# 3-ADC.net
KiCad netlist of a schematic drawn in Altium Designer
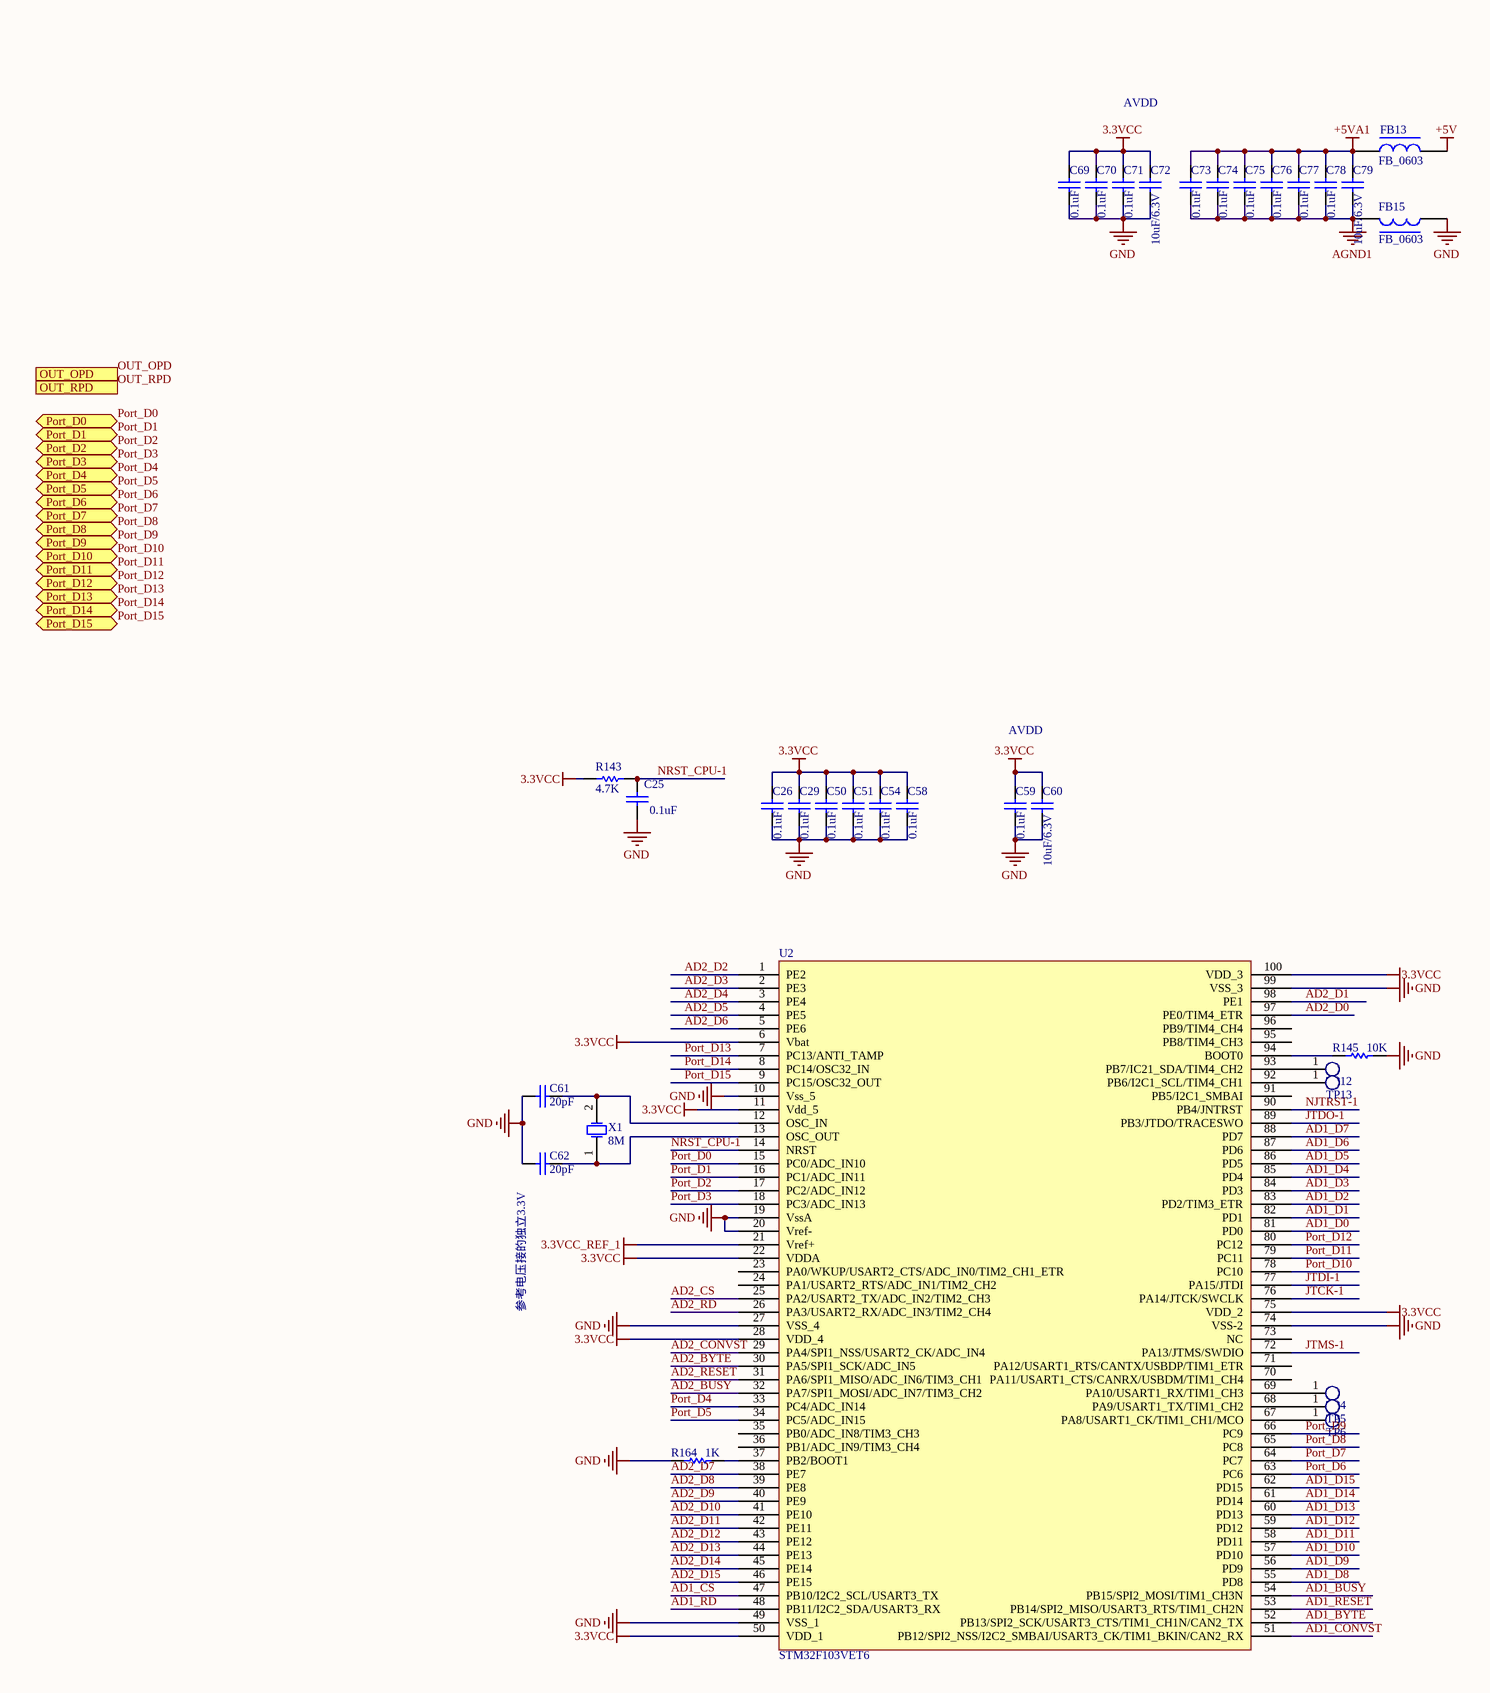
[diagram p0: 3-ADC.SchDoc, top left]
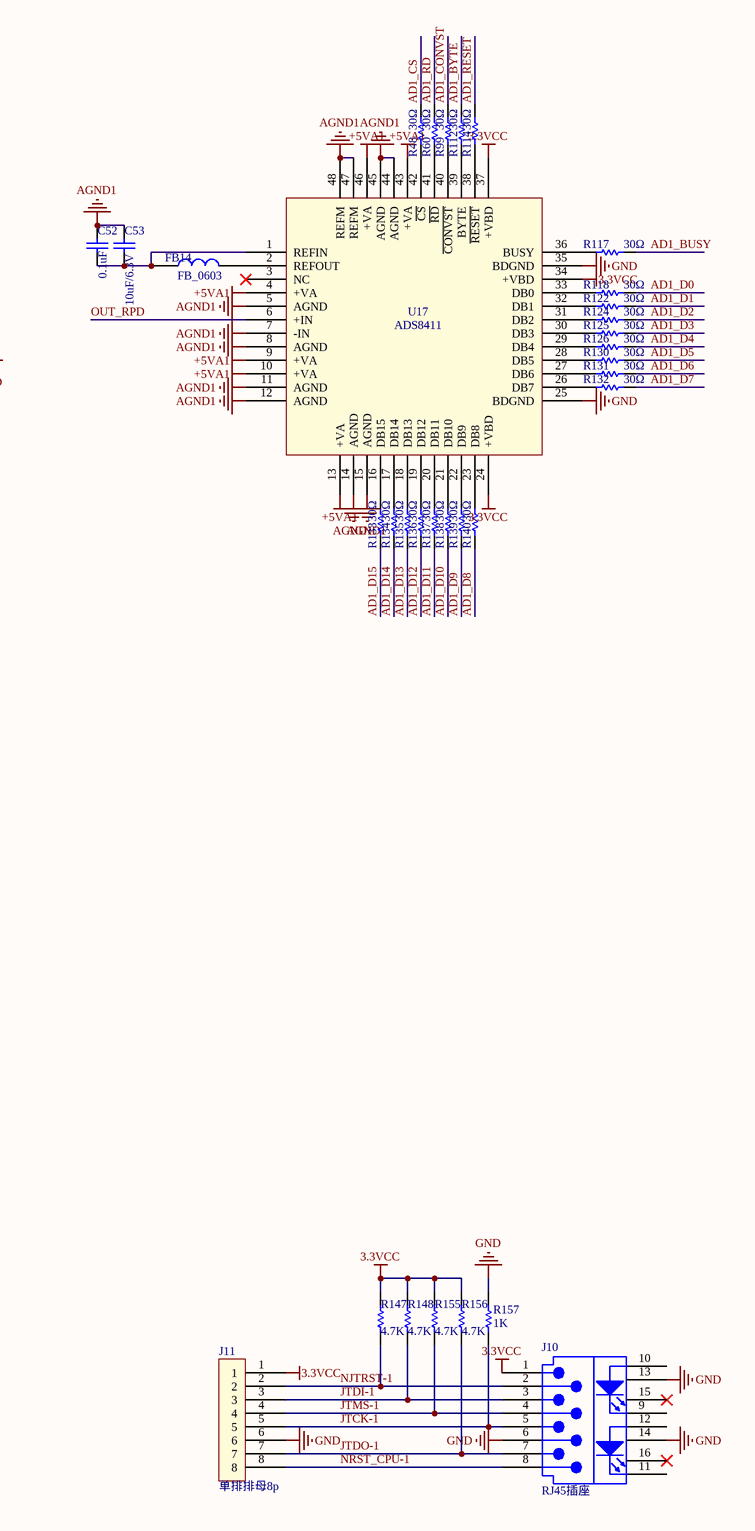
[diagram p1: 3-ADC.SchDoc, top right]
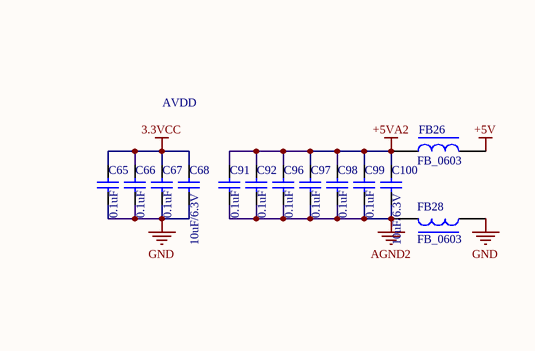
[diagram p2: 3-ADC.SchDoc, bottom left]
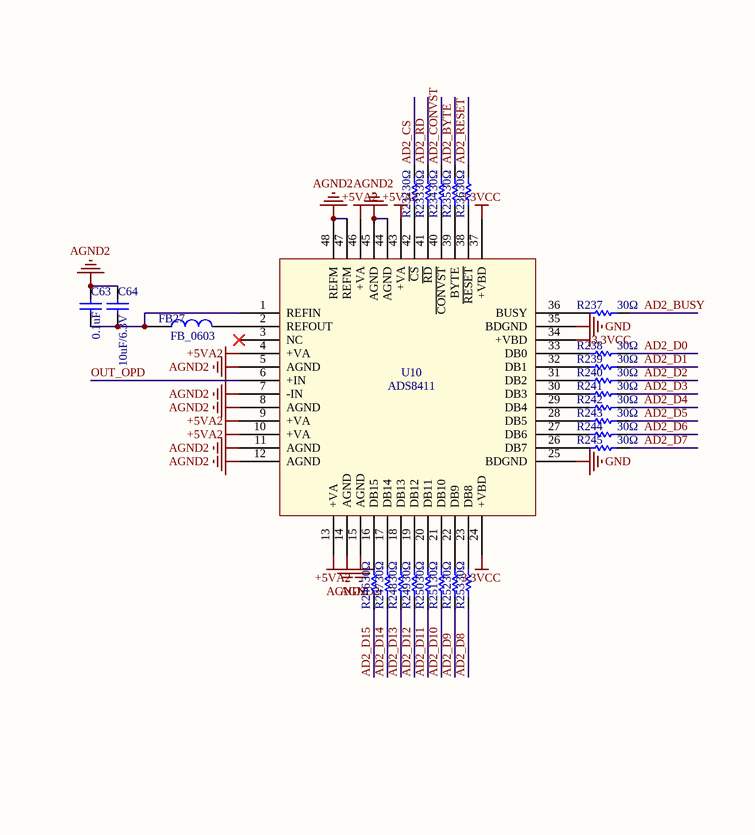
[diagram p3: 3-ADC.SchDoc, bottom right]

(export (version "E")
  (design (tool "Eeschema 10.0.6"))
  (components
    (comp (ref "C25")
      (value "0.1uF")
      (footprint "C0603")
      (description "贴片电容_GRM188R71H104KA01D_0.1uF±10%,50V,0603")
      (libsource (lib "20贴片电容0603") (part "0.1uF贴片电容"))
    )
    (comp (ref "C26")
      (value "0.1uF")
      (footprint "C0603")
      (description "贴片电容_GRM188R71H104KA01D_0.1uF±10%,50V,0603")
      (libsource (lib "20贴片电容0603") (part "0.1uF贴片电容"))
    )
    (comp (ref "C29")
      (value "0.1uF")
      (footprint "C0603")
      (description "贴片电容_GRM188R71H104KA01D_0.1uF±10%,50V,0603")
      (libsource (lib "20贴片电容0603") (part "0.1uF贴片电容"))
    )
    (comp (ref "C50")
      (value "0.1uF")
      (footprint "C0603")
      (description "贴片电容_GRM188R71H104KA01D_0.1uF±10%,50V,0603")
      (libsource (lib "20贴片电容0603") (part "0.1uF贴片电容"))
    )
    (comp (ref "C51")
      (value "0.1uF")
      (footprint "C0603")
      (description "贴片电容_GRM188R71H104KA01D_0.1uF±10%,50V,0603")
      (libsource (lib "20贴片电容0603") (part "0.1uF贴片电容"))
    )
    (comp (ref "C52")
      (value "0.1uF")
      (footprint "C0603")
      (description "贴片电容_GRM188R71H104KA01D_0.1uF±10%,50V,0603")
      (libsource (lib "20贴片电容0603") (part "0.1uF贴片电容"))
    )
    (comp (ref "C53")
      (value "10uF/6.3V")
      (footprint "C0603")
      (description "贴片电容_GRM188R60J106ME47D_10uF±20%,6.3V,0603")
      (libsource (lib "20贴片电容0603") (part "10uF贴片电容"))
    )
    (comp (ref "C54")
      (value "0.1uF")
      (footprint "C0603")
      (description "贴片电容_GRM188R71H104KA01D_0.1uF±10%,50V,0603")
      (libsource (lib "20贴片电容0603") (part "0.1uF贴片电容"))
    )
    (comp (ref "C58")
      (value "0.1uF")
      (footprint "C0603")
      (description "贴片电容_GRM188R71H104KA01D_0.1uF±10%,50V,0603")
      (libsource (lib "20贴片电容0603") (part "0.1uF贴片电容"))
    )
    (comp (ref "C59")
      (value "0.1uF")
      (footprint "C0603")
      (description "贴片电容_GRM188R71H104KA01D_0.1uF±10%,50V,0603")
      (libsource (lib "20贴片电容0603") (part "0.1uF贴片电容"))
    )
    (comp (ref "C60")
      (value "10uF/6.3V")
      (footprint "C0603")
      (description "贴片电容_GRM188R60J106ME47D_10uF±20%,6.3V,0603")
      (libsource (lib "20贴片电容0603") (part "10uF贴片电容"))
    )
    (comp (ref "C61")
      (value "20pF")
      (footprint "C0603")
      (description "贴片电容_GRM188C1H200JB01D_20pF±5%,50V,0603")
      (libsource (lib "20贴片电容0603") (part "20pF贴片电容"))
    )
    (comp (ref "C62")
      (value "20pF")
      (footprint "C0603")
      (description "贴片电容_GRM188C1H200JB01D_20pF±5%,50V,0603")
      (libsource (lib "20贴片电容0603") (part "20pF贴片电容"))
    )
    (comp (ref "C63")
      (value "0.1uF")
      (footprint "C0603")
      (description "贴片电容_GRM188R71H104KA01D_0.1uF±10%,50V,0603")
      (libsource (lib "20贴片电容0603") (part "0.1uF贴片电容"))
    )
    (comp (ref "C64")
      (value "10uF/6.3V")
      (footprint "C0603")
      (description "贴片电容_GRM188R60J106ME47D_10uF±20%,6.3V,0603")
      (libsource (lib "20贴片电容0603") (part "10uF贴片电容"))
    )
    (comp (ref "C65")
      (value "0.1uF")
      (footprint "C0603")
      (description "贴片电容_GRM188R71H104KA01D_0.1uF±10%,50V,0603")
      (libsource (lib "20贴片电容0603") (part "0.1uF贴片电容"))
    )
    (comp (ref "C66")
      (value "0.1uF")
      (footprint "C0603")
      (description "贴片电容_GRM188R71H104KA01D_0.1uF±10%,50V,0603")
      (libsource (lib "20贴片电容0603") (part "0.1uF贴片电容"))
    )
    (comp (ref "C67")
      (value "0.1uF")
      (footprint "C0603")
      (description "贴片电容_GRM188R71H104KA01D_0.1uF±10%,50V,0603")
      (libsource (lib "20贴片电容0603") (part "0.1uF贴片电容"))
    )
    (comp (ref "C68")
      (value "10uF/6.3V")
      (footprint "C0603")
      (description "贴片电容_GRM188R60J106ME47D_10uF±20%,6.3V,0603")
      (libsource (lib "20贴片电容0603") (part "10uF贴片电容"))
    )
    (comp (ref "C69")
      (value "0.1uF")
      (footprint "C0603")
      (description "贴片电容_GRM188R71H104KA01D_0.1uF±10%,50V,0603")
      (libsource (lib "20贴片电容0603") (part "0.1uF贴片电容"))
    )
    (comp (ref "C70")
      (value "0.1uF")
      (footprint "C0603")
      (description "贴片电容_GRM188R71H104KA01D_0.1uF±10%,50V,0603")
      (libsource (lib "20贴片电容0603") (part "0.1uF贴片电容"))
    )
    (comp (ref "C71")
      (value "0.1uF")
      (footprint "C0603")
      (description "贴片电容_GRM188R71H104KA01D_0.1uF±10%,50V,0603")
      (libsource (lib "20贴片电容0603") (part "0.1uF贴片电容"))
    )
    (comp (ref "C72")
      (value "10uF/6.3V")
      (footprint "C0603")
      (description "贴片电容_GRM188R60J106ME47D_10uF±20%,6.3V,0603")
      (libsource (lib "20贴片电容0603") (part "10uF贴片电容"))
    )
    (comp (ref "C73")
      (value "0.1uF")
      (footprint "C0603")
      (description "贴片电容_GRM188R71H104KA01D_0.1uF±10%,50V,0603")
      (libsource (lib "20贴片电容0603") (part "0.1uF贴片电容"))
    )
    (comp (ref "C74")
      (value "0.1uF")
      (footprint "C0603")
      (description "贴片电容_GRM188R71H104KA01D_0.1uF±10%,50V,0603")
      (libsource (lib "20贴片电容0603") (part "0.1uF贴片电容"))
    )
    (comp (ref "C75")
      (value "0.1uF")
      (footprint "C0603")
      (description "贴片电容_GRM188R71H104KA01D_0.1uF±10%,50V,0603")
      (libsource (lib "20贴片电容0603") (part "0.1uF贴片电容"))
    )
    (comp (ref "C76")
      (value "0.1uF")
      (footprint "C0603")
      (description "贴片电容_GRM188R71H104KA01D_0.1uF±10%,50V,0603")
      (libsource (lib "20贴片电容0603") (part "0.1uF贴片电容"))
    )
    (comp (ref "C77")
      (value "0.1uF")
      (footprint "C0603")
      (description "贴片电容_GRM188R71H104KA01D_0.1uF±10%,50V,0603")
      (libsource (lib "20贴片电容0603") (part "0.1uF贴片电容"))
    )
    (comp (ref "C78")
      (value "0.1uF")
      (footprint "C0603")
      (description "贴片电容_GRM188R71H104KA01D_0.1uF±10%,50V,0603")
      (libsource (lib "20贴片电容0603") (part "0.1uF贴片电容"))
    )
    (comp (ref "C79")
      (value "10uF/6.3V")
      (footprint "C0603")
      (description "贴片电容_GRM188R60J106ME47D_10uF±20%,6.3V,0603")
      (libsource (lib "20贴片电容0603") (part "10uF贴片电容"))
    )
    (comp (ref "C91")
      (value "0.1uF")
      (footprint "C0603")
      (description "贴片电容_GRM188R71H104KA01D_0.1uF±10%,50V,0603")
      (libsource (lib "20贴片电容0603") (part "0.1uF贴片电容"))
    )
    (comp (ref "C92")
      (value "0.1uF")
      (footprint "C0603")
      (description "贴片电容_GRM188R71H104KA01D_0.1uF±10%,50V,0603")
      (libsource (lib "20贴片电容0603") (part "0.1uF贴片电容"))
    )
    (comp (ref "C96")
      (value "0.1uF")
      (footprint "C0603")
      (description "贴片电容_GRM188R71H104KA01D_0.1uF±10%,50V,0603")
      (libsource (lib "20贴片电容0603") (part "0.1uF贴片电容"))
    )
    (comp (ref "C97")
      (value "0.1uF")
      (footprint "C0603")
      (description "贴片电容_GRM188R71H104KA01D_0.1uF±10%,50V,0603")
      (libsource (lib "20贴片电容0603") (part "0.1uF贴片电容"))
    )
    (comp (ref "C98")
      (value "0.1uF")
      (footprint "C0603")
      (description "贴片电容_GRM188R71H104KA01D_0.1uF±10%,50V,0603")
      (libsource (lib "20贴片电容0603") (part "0.1uF贴片电容"))
    )
    (comp (ref "C99")
      (value "0.1uF")
      (footprint "C0603")
      (description "贴片电容_GRM188R71H104KA01D_0.1uF±10%,50V,0603")
      (libsource (lib "20贴片电容0603") (part "0.1uF贴片电容"))
    )
    (comp (ref "C100")
      (value "10uF/6.3V")
      (footprint "C0603")
      (description "贴片电容_GRM188R60J106ME47D_10uF±20%,6.3V,0603")
      (libsource (lib "20贴片电容0603") (part "10uF贴片电容"))
    )
    (comp (ref "FB13")
      (value "FB_0603")
      (footprint "L0603")
      (description "贴片磁珠_100R,0603")
      (libsource (lib "32贴片磁珠0603") (part "0603贴片磁珠"))
    )
    (comp (ref "FB14")
      (value "FB_0603")
      (footprint "L0603")
      (description "贴片磁珠_100R,0603")
      (libsource (lib "32贴片磁珠0603") (part "0603贴片磁珠"))
    )
    (comp (ref "FB15")
      (value "FB_0603")
      (footprint "L0603")
      (description "贴片磁珠_100R,0603")
      (libsource (lib "32贴片磁珠0603") (part "0603贴片磁珠"))
    )
    (comp (ref "FB26")
      (value "FB_0603")
      (footprint "L0603")
      (description "贴片磁珠_100R,0603")
      (libsource (lib "32贴片磁珠0603") (part "0603贴片磁珠"))
    )
    (comp (ref "FB27")
      (value "FB_0603")
      (footprint "L0603")
      (description "贴片磁珠_100R,0603")
      (libsource (lib "32贴片磁珠0603") (part "0603贴片磁珠"))
    )
    (comp (ref "FB28")
      (value "FB_0603")
      (footprint "L0603")
      (description "贴片磁珠_100R,0603")
      (libsource (lib "32贴片磁珠0603") (part "0603贴片磁珠"))
    )
    (comp (ref "J10")
      (value "RJ45插座")
      (footprint "RJ45TH-1x1-2R54-LED")
      (description "RJ45插座_1*1,带左黄右绿灯,弯脚")
      (fields (field (name "MPN") "朱迅"))
      (libsource (lib "91连接器") (part "RJ45弯脚带灯"))
    )
    (comp (ref "J11")
      (value "单排排母8p")
      (footprint "SIP8TM-2R54")
      (description "连接器_单排排母座8p_直插,间距2.54mm")
      (fields (field (name "MPN") "WS"))
      (libsource (lib "90-连接器") (part "8p-2.54单排母座"))
    )
    (comp (ref "R48")
      (value "30Ω")
      (footprint "R0603")
      (description "贴片电阻_30Ω±5%,0603")
      (libsource (lib "10贴片电阻0603") (part "30Ω贴片电阻"))
    )
    (comp (ref "R60")
      (value "30Ω")
      (footprint "R0603")
      (description "贴片电阻_30Ω±5%,0603")
      (libsource (lib "10贴片电阻0603") (part "30Ω贴片电阻"))
    )
    (comp (ref "R99")
      (value "30Ω")
      (footprint "R0603")
      (description "贴片电阻_30Ω±5%,0603")
      (libsource (lib "10贴片电阻0603") (part "30Ω贴片电阻"))
    )
    (comp (ref "R112")
      (value "30Ω")
      (footprint "R0603")
      (description "贴片电阻_30Ω±5%,0603")
      (libsource (lib "10贴片电阻0603") (part "30Ω贴片电阻"))
    )
    (comp (ref "R114")
      (value "30Ω")
      (footprint "R0603")
      (description "贴片电阻_30Ω±5%,0603")
      (libsource (lib "10贴片电阻0603") (part "30Ω贴片电阻"))
    )
    (comp (ref "R117")
      (value "30Ω")
      (footprint "R0603")
      (description "贴片电阻_30Ω±5%,0603")
      (libsource (lib "10贴片电阻0603") (part "30Ω贴片电阻"))
    )
    (comp (ref "R118")
      (value "30Ω")
      (footprint "R0603")
      (description "贴片电阻_30Ω±5%,0603")
      (libsource (lib "10贴片电阻0603") (part "30Ω贴片电阻"))
    )
    (comp (ref "R122")
      (value "30Ω")
      (footprint "R0603")
      (description "贴片电阻_30Ω±5%,0603")
      (libsource (lib "10贴片电阻0603") (part "30Ω贴片电阻"))
    )
    (comp (ref "R124")
      (value "30Ω")
      (footprint "R0603")
      (description "贴片电阻_30Ω±5%,0603")
      (libsource (lib "10贴片电阻0603") (part "30Ω贴片电阻"))
    )
    (comp (ref "R125")
      (value "30Ω")
      (footprint "R0603")
      (description "贴片电阻_30Ω±5%,0603")
      (libsource (lib "10贴片电阻0603") (part "30Ω贴片电阻"))
    )
    (comp (ref "R126")
      (value "30Ω")
      (footprint "R0603")
      (description "贴片电阻_30Ω±5%,0603")
      (libsource (lib "10贴片电阻0603") (part "30Ω贴片电阻"))
    )
    (comp (ref "R130")
      (value "30Ω")
      (footprint "R0603")
      (description "贴片电阻_30Ω±5%,0603")
      (libsource (lib "10贴片电阻0603") (part "30Ω贴片电阻"))
    )
    (comp (ref "R131")
      (value "30Ω")
      (footprint "R0603")
      (description "贴片电阻_30Ω±5%,0603")
      (libsource (lib "10贴片电阻0603") (part "30Ω贴片电阻"))
    )
    (comp (ref "R132")
      (value "30Ω")
      (footprint "R0603")
      (description "贴片电阻_30Ω±5%,0603")
      (libsource (lib "10贴片电阻0603") (part "30Ω贴片电阻"))
    )
    (comp (ref "R133")
      (value "30Ω")
      (footprint "R0603")
      (description "贴片电阻_30Ω±5%,0603")
      (libsource (lib "10贴片电阻0603") (part "30Ω贴片电阻"))
    )
    (comp (ref "R134")
      (value "30Ω")
      (footprint "R0603")
      (description "贴片电阻_30Ω±5%,0603")
      (libsource (lib "10贴片电阻0603") (part "30Ω贴片电阻"))
    )
    (comp (ref "R135")
      (value "30Ω")
      (footprint "R0603")
      (description "贴片电阻_30Ω±5%,0603")
      (libsource (lib "10贴片电阻0603") (part "30Ω贴片电阻"))
    )
    (comp (ref "R136")
      (value "30Ω")
      (footprint "R0603")
      (description "贴片电阻_30Ω±5%,0603")
      (libsource (lib "10贴片电阻0603") (part "30Ω贴片电阻"))
    )
    (comp (ref "R137")
      (value "30Ω")
      (footprint "R0603")
      (description "贴片电阻_30Ω±5%,0603")
      (libsource (lib "10贴片电阻0603") (part "30Ω贴片电阻"))
    )
    (comp (ref "R138")
      (value "30Ω")
      (footprint "R0603")
      (description "贴片电阻_30Ω±5%,0603")
      (libsource (lib "10贴片电阻0603") (part "30Ω贴片电阻"))
    )
    (comp (ref "R139")
      (value "30Ω")
      (footprint "R0603")
      (description "贴片电阻_30Ω±5%,0603")
      (libsource (lib "10贴片电阻0603") (part "30Ω贴片电阻"))
    )
    (comp (ref "R140")
      (value "30Ω")
      (footprint "R0603")
      (description "贴片电阻_30Ω±5%,0603")
      (libsource (lib "10贴片电阻0603") (part "30Ω贴片电阻"))
    )
    (comp (ref "R143")
      (value "4.7K")
      (footprint "R0603")
      (description "贴片电阻_4.7K±5%,0603")
      (libsource (lib "10贴片电阻0603") (part "4.7K贴片电阻"))
    )
    (comp (ref "R145")
      (value "10K")
      (footprint "R0603")
      (description "贴片电阻_10K±5%,0603")
      (libsource (lib "10贴片电阻0603") (part "10K贴片电阻"))
    )
    (comp (ref "R147")
      (value "4.7K")
      (footprint "R0603")
      (description "贴片电阻_4.7K±5%,0603")
      (libsource (lib "10贴片电阻0603") (part "4.7K贴片电阻"))
    )
    (comp (ref "R148")
      (value "4.7K")
      (footprint "R0603")
      (description "贴片电阻_4.7K±5%,0603")
      (libsource (lib "10贴片电阻0603") (part "4.7K贴片电阻"))
    )
    (comp (ref "R155")
      (value "4.7K")
      (footprint "R0603")
      (description "贴片电阻_4.7K±5%,0603")
      (libsource (lib "10贴片电阻0603") (part "4.7K贴片电阻"))
    )
    (comp (ref "R156")
      (value "4.7K")
      (footprint "R0603")
      (description "贴片电阻_4.7K±5%,0603")
      (libsource (lib "10贴片电阻0603") (part "4.7K贴片电阻"))
    )
    (comp (ref "R157")
      (value "1K")
      (footprint "R0603")
      (description "贴片电阻_1K±5%,0603")
      (libsource (lib "10贴片电阻0603") (part "1K贴片电阻"))
    )
    (comp (ref "R164")
      (value "1K")
      (footprint "R0603")
      (description "贴片电阻_1K±5%,0603")
      (libsource (lib "10贴片电阻0603") (part "1K贴片电阻"))
    )
    (comp (ref "R232")
      (value "30Ω")
      (footprint "R0603")
      (description "贴片电阻_30Ω±5%,0603")
      (libsource (lib "10贴片电阻0603") (part "30Ω贴片电阻"))
    )
    (comp (ref "R233")
      (value "30Ω")
      (footprint "R0603")
      (description "贴片电阻_30Ω±5%,0603")
      (libsource (lib "10贴片电阻0603") (part "30Ω贴片电阻"))
    )
    (comp (ref "R234")
      (value "30Ω")
      (footprint "R0603")
      (description "贴片电阻_30Ω±5%,0603")
      (libsource (lib "10贴片电阻0603") (part "30Ω贴片电阻"))
    )
    (comp (ref "R235")
      (value "30Ω")
      (footprint "R0603")
      (description "贴片电阻_30Ω±5%,0603")
      (libsource (lib "10贴片电阻0603") (part "30Ω贴片电阻"))
    )
    (comp (ref "R236")
      (value "30Ω")
      (footprint "R0603")
      (description "贴片电阻_30Ω±5%,0603")
      (libsource (lib "10贴片电阻0603") (part "30Ω贴片电阻"))
    )
    (comp (ref "R237")
      (value "30Ω")
      (footprint "R0603")
      (description "贴片电阻_30Ω±5%,0603")
      (libsource (lib "10贴片电阻0603") (part "30Ω贴片电阻"))
    )
    (comp (ref "R238")
      (value "30Ω")
      (footprint "R0603")
      (description "贴片电阻_30Ω±5%,0603")
      (libsource (lib "10贴片电阻0603") (part "30Ω贴片电阻"))
    )
    (comp (ref "R239")
      (value "30Ω")
      (footprint "R0603")
      (description "贴片电阻_30Ω±5%,0603")
      (libsource (lib "10贴片电阻0603") (part "30Ω贴片电阻"))
    )
    (comp (ref "R240")
      (value "30Ω")
      (footprint "R0603")
      (description "贴片电阻_30Ω±5%,0603")
      (libsource (lib "10贴片电阻0603") (part "30Ω贴片电阻"))
    )
    (comp (ref "R241")
      (value "30Ω")
      (footprint "R0603")
      (description "贴片电阻_30Ω±5%,0603")
      (libsource (lib "10贴片电阻0603") (part "30Ω贴片电阻"))
    )
    (comp (ref "R242")
      (value "30Ω")
      (footprint "R0603")
      (description "贴片电阻_30Ω±5%,0603")
      (libsource (lib "10贴片电阻0603") (part "30Ω贴片电阻"))
    )
    (comp (ref "R243")
      (value "30Ω")
      (footprint "R0603")
      (description "贴片电阻_30Ω±5%,0603")
      (libsource (lib "10贴片电阻0603") (part "30Ω贴片电阻"))
    )
    (comp (ref "R244")
      (value "30Ω")
      (footprint "R0603")
      (description "贴片电阻_30Ω±5%,0603")
      (libsource (lib "10贴片电阻0603") (part "30Ω贴片电阻"))
    )
    (comp (ref "R245")
      (value "30Ω")
      (footprint "R0603")
      (description "贴片电阻_30Ω±5%,0603")
      (libsource (lib "10贴片电阻0603") (part "30Ω贴片电阻"))
    )
    (comp (ref "R246")
      (value "30Ω")
      (footprint "R0603")
      (description "贴片电阻_30Ω±5%,0603")
      (libsource (lib "10贴片电阻0603") (part "30Ω贴片电阻"))
    )
    (comp (ref "R247")
      (value "30Ω")
      (footprint "R0603")
      (description "贴片电阻_30Ω±5%,0603")
      (libsource (lib "10贴片电阻0603") (part "30Ω贴片电阻"))
    )
    (comp (ref "R248")
      (value "30Ω")
      (footprint "R0603")
      (description "贴片电阻_30Ω±5%,0603")
      (libsource (lib "10贴片电阻0603") (part "30Ω贴片电阻"))
    )
    (comp (ref "R249")
      (value "30Ω")
      (footprint "R0603")
      (description "贴片电阻_30Ω±5%,0603")
      (libsource (lib "10贴片电阻0603") (part "30Ω贴片电阻"))
    )
    (comp (ref "R250")
      (value "30Ω")
      (footprint "R0603")
      (description "贴片电阻_30Ω±5%,0603")
      (libsource (lib "10贴片电阻0603") (part "30Ω贴片电阻"))
    )
    (comp (ref "R251")
      (value "30Ω")
      (footprint "R0603")
      (description "贴片电阻_30Ω±5%,0603")
      (libsource (lib "10贴片电阻0603") (part "30Ω贴片电阻"))
    )
    (comp (ref "R252")
      (value "30Ω")
      (footprint "R0603")
      (description "贴片电阻_30Ω±5%,0603")
      (libsource (lib "10贴片电阻0603") (part "30Ω贴片电阻"))
    )
    (comp (ref "R253")
      (value "30Ω")
      (footprint "R0603")
      (description "贴片电阻_30Ω±5%,0603")
      (libsource (lib "10贴片电阻0603") (part "30Ω贴片电阻"))
    )
    (comp (ref "TP4")
      (value "TEST")
      (footprint "TP0R8")
      (description "表贴测试点0.8mm")
      (libsource (lib "92-其他（穿心电容，test等）") (part "TP0.8mm"))
    )
    (comp (ref "TP5")
      (value "TEST")
      (footprint "TP0R8")
      (description "表贴测试点0.8mm")
      (libsource (lib "92-其他（穿心电容，test等）") (part "TP0.8mm"))
    )
    (comp (ref "TP6")
      (value "TEST")
      (footprint "TP0R8")
      (description "表贴测试点0.8mm")
      (libsource (lib "92-其他（穿心电容，test等）") (part "TP0.8mm"))
    )
    (comp (ref "TP12")
      (value "TEST")
      (footprint "TP0R8")
      (description "表贴测试点0.8mm")
      (libsource (lib "92-其他（穿心电容，test等）") (part "TP0.8mm"))
    )
    (comp (ref "TP13")
      (value "TEST")
      (footprint "TP0R8")
      (description "表贴测试点0.8mm")
      (libsource (lib "92-其他（穿心电容，test等）") (part "TP0.8mm"))
    )
    (comp (ref "U2")
      (value "STM32F103VET6")
      (footprint "LQFP100_0R5_14x14")
      (description "MCU_STM32F103VET6_32 bit, LQFP100")
      (libsource (lib "71单片机") (part "STM32F103VET"))
    )
    (comp (ref "U10")
      (value "ADS8411")
      (footprint "TQFN48-0R5-7X7")
      (description "模数转换芯片_ADS8411_16-Bit,2MSPS,QFN48")
      (libsource (lib "88模数转换芯片") (part "ADS8411"))
    )
    (comp (ref "U17")
      (value "ADS8411")
      (footprint "TQFN48-0R5-7X7")
      (description "模数转换芯片_ADS8411_16-Bit,2MSPS,QFN48")
      (libsource (lib "88模数转换芯片") (part "ADS8411"))
    )
    (comp (ref "X1")
      (value "8M")
      (footprint "CRY2SM-6R0x3R5")
      (description "贴片无源晶体_8MHz,封装6035")
      (libsource (lib "60振荡器") (part "8M贴片无源晶体"))
    )
  )
  (nets
    (net (code "1") (name "+5V") (class "Default")
      (node (ref "FB13") (pin "2") (pinfunction "2_2") (pintype "passive"))
      (node (ref "FB26") (pin "2") (pinfunction "2_2") (pintype "passive"))
    )
    (net (code "2") (name "+5VA1") (class "Default")
      (node (ref "C73") (pin "2") (pinfunction "2_2") (pintype "passive"))
      (node (ref "C74") (pin "2") (pinfunction "2_2") (pintype "passive"))
      (node (ref "C75") (pin "2") (pinfunction "2_2") (pintype "passive"))
      (node (ref "C76") (pin "2") (pinfunction "2_2") (pintype "passive"))
      (node (ref "C77") (pin "2") (pinfunction "2_2") (pintype "passive"))
      (node (ref "C78") (pin "2") (pinfunction "2_2") (pintype "passive"))
      (node (ref "C79") (pin "2") (pinfunction "2_2") (pintype "passive"))
      (node (ref "FB13") (pin "1") (pinfunction "1_1") (pintype "passive"))
      (node (ref "U17") (pin "10") (pinfunction "+VA_10") (pintype "passive"))
      (node (ref "U17") (pin "13") (pinfunction "+VA_13") (pintype "passive"))
      (node (ref "U17") (pin "4") (pinfunction "+VA_4") (pintype "passive"))
      (node (ref "U17") (pin "43") (pinfunction "+VA_43") (pintype "passive"))
      (node (ref "U17") (pin "46") (pinfunction "+VA_46") (pintype "passive"))
      (node (ref "U17") (pin "9") (pinfunction "+VA_9") (pintype "passive"))
    )
    (net (code "3") (name "+5VA2") (class "Default")
      (node (ref "C100") (pin "2") (pinfunction "2_2") (pintype "passive"))
      (node (ref "C91") (pin "2") (pinfunction "2_2") (pintype "passive"))
      (node (ref "C92") (pin "2") (pinfunction "2_2") (pintype "passive"))
      (node (ref "C96") (pin "2") (pinfunction "2_2") (pintype "passive"))
      (node (ref "C97") (pin "2") (pinfunction "2_2") (pintype "passive"))
      (node (ref "C98") (pin "2") (pinfunction "2_2") (pintype "passive"))
      (node (ref "C99") (pin "2") (pinfunction "2_2") (pintype "passive"))
      (node (ref "FB26") (pin "1") (pinfunction "1_1") (pintype "passive"))
      (node (ref "U10") (pin "10") (pinfunction "+VA_10") (pintype "passive"))
      (node (ref "U10") (pin "13") (pinfunction "+VA_13") (pintype "passive"))
      (node (ref "U10") (pin "4") (pinfunction "+VA_4") (pintype "passive"))
      (node (ref "U10") (pin "43") (pinfunction "+VA_43") (pintype "passive"))
      (node (ref "U10") (pin "46") (pinfunction "+VA_46") (pintype "passive"))
      (node (ref "U10") (pin "9") (pinfunction "+VA_9") (pintype "passive"))
    )
    (net (code "4") (name "/AD1_BUSY") (class "Default")
      (node (ref "R117") (pin "2") (pinfunction "2_2") (pintype "passive"))
      (node (ref "U2") (pin "54") (pinfunction "PB15/SPI2_MOSI/TIM1_CH3N_54") (pintype "passive"))
    )
    (net (code "5") (name "/AD1_BYTE") (class "Default")
      (node (ref "R112") (pin "2") (pinfunction "2_2") (pintype "passive"))
      (node (ref "U2") (pin "52") (pinfunction "PB13/SPI2_SCK/USART3_CTS/TIM1_CH1N/CAN2_TX_52") (pintype "passive"))
    )
    (net (code "6") (name "/AD1_CONVST") (class "Default")
      (node (ref "R99") (pin "2") (pinfunction "2_2") (pintype "passive"))
      (node (ref "U2") (pin "51") (pinfunction "PB12/SPI2_NSS/I2C2_SMBAI/USART3_CK/TIM1_BKIN/CAN2_RX_51") (pintype "passive"))
    )
    (net (code "7") (name "/AD1_CS") (class "Default")
      (node (ref "R48") (pin "2") (pinfunction "2_2") (pintype "passive"))
      (node (ref "U2") (pin "47") (pinfunction "PB10/I2C2_SCL/USART3_TX_47") (pintype "passive"))
    )
    (net (code "8") (name "/AD1_D0") (class "Default")
      (node (ref "R118") (pin "2") (pinfunction "2_2") (pintype "passive"))
      (node (ref "U2") (pin "81") (pinfunction "PD0_81") (pintype "passive"))
    )
    (net (code "9") (name "/AD1_D1") (class "Default")
      (node (ref "R122") (pin "2") (pinfunction "2_2") (pintype "passive"))
      (node (ref "U2") (pin "82") (pinfunction "PD1_82") (pintype "passive"))
    )
    (net (code "10") (name "/AD1_D2") (class "Default")
      (node (ref "R124") (pin "2") (pinfunction "2_2") (pintype "passive"))
      (node (ref "U2") (pin "83") (pinfunction "PD2/TIM3_ETR_83") (pintype "passive"))
    )
    (net (code "11") (name "/AD1_D3") (class "Default")
      (node (ref "R125") (pin "2") (pinfunction "2_2") (pintype "passive"))
      (node (ref "U2") (pin "84") (pinfunction "PD3_84") (pintype "passive"))
    )
    (net (code "12") (name "/AD1_D4") (class "Default")
      (node (ref "R126") (pin "2") (pinfunction "2_2") (pintype "passive"))
      (node (ref "U2") (pin "85") (pinfunction "PD4_85") (pintype "passive"))
    )
    (net (code "13") (name "/AD1_D5") (class "Default")
      (node (ref "R130") (pin "2") (pinfunction "2_2") (pintype "passive"))
      (node (ref "U2") (pin "86") (pinfunction "PD5_86") (pintype "passive"))
    )
    (net (code "14") (name "/AD1_D6") (class "Default")
      (node (ref "R131") (pin "2") (pinfunction "2_2") (pintype "passive"))
      (node (ref "U2") (pin "87") (pinfunction "PD6_87") (pintype "passive"))
    )
    (net (code "15") (name "/AD1_D7") (class "Default")
      (node (ref "R132") (pin "2") (pinfunction "2_2") (pintype "passive"))
      (node (ref "U2") (pin "88") (pinfunction "PD7_88") (pintype "passive"))
    )
    (net (code "16") (name "/AD1_D8") (class "Default")
      (node (ref "R140") (pin "1") (pinfunction "1_1") (pintype "passive"))
      (node (ref "U2") (pin "55") (pinfunction "PD8_55") (pintype "passive"))
    )
    (net (code "17") (name "/AD1_D9") (class "Default")
      (node (ref "R139") (pin "1") (pinfunction "1_1") (pintype "passive"))
      (node (ref "U2") (pin "56") (pinfunction "PD9_56") (pintype "passive"))
    )
    (net (code "18") (name "/AD1_D10") (class "Default")
      (node (ref "R138") (pin "1") (pinfunction "1_1") (pintype "passive"))
      (node (ref "U2") (pin "57") (pinfunction "PD10_57") (pintype "passive"))
    )
    (net (code "19") (name "/AD1_D11") (class "Default")
      (node (ref "R137") (pin "1") (pinfunction "1_1") (pintype "passive"))
      (node (ref "U2") (pin "58") (pinfunction "PD11_58") (pintype "passive"))
    )
    (net (code "20") (name "/AD1_D12") (class "Default")
      (node (ref "R136") (pin "1") (pinfunction "1_1") (pintype "passive"))
      (node (ref "U2") (pin "59") (pinfunction "PD12_59") (pintype "passive"))
    )
    (net (code "21") (name "/AD1_D13") (class "Default")
      (node (ref "R135") (pin "1") (pinfunction "1_1") (pintype "passive"))
      (node (ref "U2") (pin "60") (pinfunction "PD13_60") (pintype "passive"))
    )
    (net (code "22") (name "/AD1_D14") (class "Default")
      (node (ref "R134") (pin "1") (pinfunction "1_1") (pintype "passive"))
      (node (ref "U2") (pin "61") (pinfunction "PD14_61") (pintype "passive"))
    )
    (net (code "23") (name "/AD1_D15") (class "Default")
      (node (ref "R133") (pin "1") (pinfunction "1_1") (pintype "passive"))
      (node (ref "U2") (pin "62") (pinfunction "PD15_62") (pintype "passive"))
    )
    (net (code "24") (name "/AD1_RD") (class "Default")
      (node (ref "R60") (pin "2") (pinfunction "2_2") (pintype "passive"))
      (node (ref "U2") (pin "48") (pinfunction "PB11/I2C2_SDA/USART3_RX_48") (pintype "passive"))
    )
    (net (code "25") (name "/AD1_RESET") (class "Default")
      (node (ref "R114") (pin "2") (pinfunction "2_2") (pintype "passive"))
      (node (ref "U2") (pin "53") (pinfunction "PB14/SPI2_MISO/USART3_RTS/TIM1_CH2N_53") (pintype "passive"))
    )
    (net (code "26") (name "/AD2_BUSY") (class "Default")
      (node (ref "R237") (pin "2") (pinfunction "2_2") (pintype "passive"))
      (node (ref "U2") (pin "32") (pinfunction "PA7/SPI1_MOSI/ADC_IN7/TIM3_CH2_32") (pintype "passive"))
    )
    (net (code "27") (name "/AD2_BYTE") (class "Default")
      (node (ref "R235") (pin "2") (pinfunction "2_2") (pintype "passive"))
      (node (ref "U2") (pin "30") (pinfunction "PA5/SPI1_SCK/ADC_IN5_30") (pintype "passive"))
    )
    (net (code "28") (name "/AD2_CONVST") (class "Default")
      (node (ref "R234") (pin "2") (pinfunction "2_2") (pintype "passive"))
      (node (ref "U2") (pin "29") (pinfunction "PA4/SPI1_NSS/USART2_CK/ADC_IN4_29") (pintype "passive"))
    )
    (net (code "29") (name "/AD2_CS") (class "Default")
      (node (ref "R232") (pin "2") (pinfunction "2_2") (pintype "passive"))
      (node (ref "U2") (pin "25") (pinfunction "PA2/USART2_TX/ADC_IN2/TIM2_CH3_25") (pintype "passive"))
    )
    (net (code "30") (name "/AD2_D0") (class "Default")
      (node (ref "R238") (pin "2") (pinfunction "2_2") (pintype "passive"))
      (node (ref "U2") (pin "97") (pinfunction "PE0/TIM4_ETR_97") (pintype "passive"))
    )
    (net (code "31") (name "/AD2_D1") (class "Default")
      (node (ref "R239") (pin "2") (pinfunction "2_2") (pintype "passive"))
      (node (ref "U2") (pin "98") (pinfunction "PE1_98") (pintype "passive"))
    )
    (net (code "32") (name "/AD2_D2") (class "Default")
      (node (ref "R240") (pin "2") (pinfunction "2_2") (pintype "passive"))
      (node (ref "U2") (pin "1") (pinfunction "PE2_1") (pintype "passive"))
    )
    (net (code "33") (name "/AD2_D3") (class "Default")
      (node (ref "R241") (pin "2") (pinfunction "2_2") (pintype "passive"))
      (node (ref "U2") (pin "2") (pinfunction "PE3_2") (pintype "passive"))
    )
    (net (code "34") (name "/AD2_D4") (class "Default")
      (node (ref "R242") (pin "2") (pinfunction "2_2") (pintype "passive"))
      (node (ref "U2") (pin "3") (pinfunction "PE4_3") (pintype "passive"))
    )
    (net (code "35") (name "/AD2_D5") (class "Default")
      (node (ref "R243") (pin "2") (pinfunction "2_2") (pintype "passive"))
      (node (ref "U2") (pin "4") (pinfunction "PE5_4") (pintype "passive"))
    )
    (net (code "36") (name "/AD2_D6") (class "Default")
      (node (ref "R244") (pin "2") (pinfunction "2_2") (pintype "passive"))
      (node (ref "U2") (pin "5") (pinfunction "PE6_5") (pintype "passive"))
    )
    (net (code "37") (name "/AD2_D7") (class "Default")
      (node (ref "R245") (pin "2") (pinfunction "2_2") (pintype "passive"))
      (node (ref "U2") (pin "38") (pinfunction "PE7_38") (pintype "passive"))
    )
    (net (code "38") (name "/AD2_D8") (class "Default")
      (node (ref "R253") (pin "1") (pinfunction "1_1") (pintype "passive"))
      (node (ref "U2") (pin "39") (pinfunction "PE8_39") (pintype "passive"))
    )
    (net (code "39") (name "/AD2_D9") (class "Default")
      (node (ref "R252") (pin "1") (pinfunction "1_1") (pintype "passive"))
      (node (ref "U2") (pin "40") (pinfunction "PE9_40") (pintype "passive"))
    )
    (net (code "40") (name "/AD2_D10") (class "Default")
      (node (ref "R251") (pin "1") (pinfunction "1_1") (pintype "passive"))
      (node (ref "U2") (pin "41") (pinfunction "PE10_41") (pintype "passive"))
    )
    (net (code "41") (name "/AD2_D11") (class "Default")
      (node (ref "R250") (pin "1") (pinfunction "1_1") (pintype "passive"))
      (node (ref "U2") (pin "42") (pinfunction "PE11_42") (pintype "passive"))
    )
    (net (code "42") (name "/AD2_D12") (class "Default")
      (node (ref "R249") (pin "1") (pinfunction "1_1") (pintype "passive"))
      (node (ref "U2") (pin "43") (pinfunction "PE12_43") (pintype "passive"))
    )
    (net (code "43") (name "/AD2_D13") (class "Default")
      (node (ref "R248") (pin "1") (pinfunction "1_1") (pintype "passive"))
      (node (ref "U2") (pin "44") (pinfunction "PE13_44") (pintype "passive"))
    )
    (net (code "44") (name "/AD2_D14") (class "Default")
      (node (ref "R247") (pin "1") (pinfunction "1_1") (pintype "passive"))
      (node (ref "U2") (pin "45") (pinfunction "PE14_45") (pintype "passive"))
    )
    (net (code "45") (name "/AD2_D15") (class "Default")
      (node (ref "R246") (pin "1") (pinfunction "1_1") (pintype "passive"))
      (node (ref "U2") (pin "46") (pinfunction "PE15_46") (pintype "passive"))
    )
    (net (code "46") (name "/AD2_RD") (class "Default")
      (node (ref "R233") (pin "2") (pinfunction "2_2") (pintype "passive"))
      (node (ref "U2") (pin "26") (pinfunction "PA3/USART2_RX/ADC_IN3/TIM2_CH4_26") (pintype "passive"))
    )
    (net (code "47") (name "/AD2_RESET") (class "Default")
      (node (ref "R236") (pin "2") (pinfunction "2_2") (pintype "passive"))
      (node (ref "U2") (pin "31") (pinfunction "PA6/SPI1_MISO/ADC_IN6/TIM3_CH1_31") (pintype "passive"))
    )
    (net (code "48") (name "/JTCK-1") (class "Default")
      (node (ref "J10") (pin "5") (pinfunction "NC_5") (pintype "passive"))
      (node (ref "J11") (pin "5") (pinfunction "5_5") (pintype "passive"))
      (node (ref "R157") (pin "2") (pinfunction "2_2") (pintype "passive"))
      (node (ref "U2") (pin "76") (pinfunction "PA14/JTCK/SWCLK_76") (pintype "passive"))
    )
    (net (code "49") (name "/JTDI-1") (class "Default")
      (node (ref "J10") (pin "3") (pinfunction "RX+_3") (pintype "passive"))
      (node (ref "J11") (pin "3") (pinfunction "3_3") (pintype "passive"))
      (node (ref "R148") (pin "1") (pinfunction "1_1") (pintype "passive"))
      (node (ref "U2") (pin "77") (pinfunction "PA15/JTDI_77") (pintype "passive"))
    )
    (net (code "50") (name "/JTDO-1") (class "Default")
      (node (ref "J10") (pin "7") (pinfunction "NC_7") (pintype "passive"))
      (node (ref "J11") (pin "7") (pinfunction "7_7") (pintype "passive"))
      (node (ref "R156") (pin "1") (pinfunction "1_1") (pintype "passive"))
      (node (ref "U2") (pin "89") (pinfunction "PB3/JTDO/TRACESWO_89") (pintype "passive"))
    )
    (net (code "51") (name "/JTMS-1") (class "Default")
      (node (ref "J10") (pin "4") (pinfunction "NC_4") (pintype "passive"))
      (node (ref "J11") (pin "4") (pinfunction "4_4") (pintype "passive"))
      (node (ref "R155") (pin "1") (pinfunction "1_1") (pintype "passive"))
      (node (ref "U2") (pin "72") (pinfunction "PA13/JTMS/SWDIO_72") (pintype "passive"))
    )
    (net (code "52") (name "/NJTRST-1") (class "Default")
      (node (ref "J10") (pin "2") (pinfunction "TX-_2") (pintype "passive"))
      (node (ref "J11") (pin "2") (pinfunction "2_2") (pintype "passive"))
      (node (ref "R147") (pin "1") (pinfunction "1_1") (pintype "passive"))
      (node (ref "U2") (pin "90") (pinfunction "PB4/JNTRST_90") (pintype "passive"))
    )
    (net (code "53") (name "/NRST_CPU-1") (class "Default")
      (node (ref "C25") (pin "2") (pinfunction "2_2") (pintype "passive"))
      (node (ref "J10") (pin "8") (pinfunction "NC_8") (pintype "passive"))
      (node (ref "J11") (pin "8") (pinfunction "8_8") (pintype "passive"))
      (node (ref "R143") (pin "1") (pinfunction "1_1") (pintype "passive"))
      (node (ref "U2") (pin "14") (pinfunction "NRST_14") (pintype "passive"))
    )
    (net (code "54") (name "/OUT_OPD") (class "Default")
      (node (ref "U10") (pin "6") (pinfunction "+IN_6") (pintype "passive"))
    )
    (net (code "55") (name "/OUT_RPD") (class "Default")
      (node (ref "U17") (pin "6") (pinfunction "+IN_6") (pintype "passive"))
    )
    (net (code "56") (name "/Port_D0") (class "Default")
      (node (ref "U2") (pin "15") (pinfunction "PC0/ADC_IN10_15") (pintype "passive"))
    )
    (net (code "57") (name "/Port_D1") (class "Default")
      (node (ref "U2") (pin "16") (pinfunction "PC1/ADC_IN11_16") (pintype "passive"))
    )
    (net (code "58") (name "/Port_D2") (class "Default")
      (node (ref "U2") (pin "17") (pinfunction "PC2/ADC_IN12_17") (pintype "passive"))
    )
    (net (code "59") (name "/Port_D3") (class "Default")
      (node (ref "U2") (pin "18") (pinfunction "PC3/ADC_IN13_18") (pintype "passive"))
    )
    (net (code "60") (name "/Port_D4") (class "Default")
      (node (ref "U2") (pin "33") (pinfunction "PC4/ADC_IN14_33") (pintype "passive"))
    )
    (net (code "61") (name "/Port_D5") (class "Default")
      (node (ref "U2") (pin "34") (pinfunction "PC5/ADC_IN15_34") (pintype "passive"))
    )
    (net (code "62") (name "/Port_D6") (class "Default")
      (node (ref "U2") (pin "63") (pinfunction "PC6_63") (pintype "passive"))
    )
    (net (code "63") (name "/Port_D7") (class "Default")
      (node (ref "U2") (pin "64") (pinfunction "PC7_64") (pintype "passive"))
    )
    (net (code "64") (name "/Port_D8") (class "Default")
      (node (ref "U2") (pin "65") (pinfunction "PC8_65") (pintype "passive"))
    )
    (net (code "65") (name "/Port_D9") (class "Default")
      (node (ref "U2") (pin "66") (pinfunction "PC9_66") (pintype "passive"))
    )
    (net (code "66") (name "/Port_D10") (class "Default")
      (node (ref "U2") (pin "78") (pinfunction "PC10_78") (pintype "passive"))
    )
    (net (code "67") (name "/Port_D11") (class "Default")
      (node (ref "U2") (pin "79") (pinfunction "PC11_79") (pintype "passive"))
    )
    (net (code "68") (name "/Port_D12") (class "Default")
      (node (ref "U2") (pin "80") (pinfunction "PC12_80") (pintype "passive"))
    )
    (net (code "69") (name "/Port_D13") (class "Default")
      (node (ref "U2") (pin "7") (pinfunction "PC13/ANTI_TAMP_7") (pintype "passive"))
    )
    (net (code "70") (name "/Port_D14") (class "Default")
      (node (ref "U2") (pin "8") (pinfunction "PC14/OSC32_IN_8") (pintype "passive"))
    )
    (net (code "71") (name "/Port_D15") (class "Default")
      (node (ref "U2") (pin "9") (pinfunction "PC15/OSC32_OUT_9") (pintype "passive"))
    )
    (net (code "72") (name "3.3VCC") (class "Default")
      (node (ref "C26") (pin "2") (pinfunction "2_2") (pintype "passive"))
      (node (ref "C29") (pin "2") (pinfunction "2_2") (pintype "passive"))
      (node (ref "C50") (pin "2") (pinfunction "2_2") (pintype "passive"))
      (node (ref "C51") (pin "2") (pinfunction "2_2") (pintype "passive"))
      (node (ref "C54") (pin "2") (pinfunction "2_2") (pintype "passive"))
      (node (ref "C58") (pin "2") (pinfunction "2_2") (pintype "passive"))
      (node (ref "C59") (pin "2") (pinfunction "2_2") (pintype "passive"))
      (node (ref "C60") (pin "2") (pinfunction "2_2") (pintype "passive"))
      (node (ref "C65") (pin "2") (pinfunction "2_2") (pintype "passive"))
      (node (ref "C66") (pin "2") (pinfunction "2_2") (pintype "passive"))
      (node (ref "C67") (pin "2") (pinfunction "2_2") (pintype "passive"))
      (node (ref "C68") (pin "2") (pinfunction "2_2") (pintype "passive"))
      (node (ref "C69") (pin "2") (pinfunction "2_2") (pintype "passive"))
      (node (ref "C70") (pin "2") (pinfunction "2_2") (pintype "passive"))
      (node (ref "C71") (pin "2") (pinfunction "2_2") (pintype "passive"))
      (node (ref "C72") (pin "2") (pinfunction "2_2") (pintype "passive"))
      (node (ref "J10") (pin "1") (pinfunction "TX+_1") (pintype "passive"))
      (node (ref "J11") (pin "1") (pinfunction "1_1") (pintype "passive"))
      (node (ref "R143") (pin "2") (pinfunction "2_2") (pintype "passive"))
      (node (ref "R147") (pin "2") (pinfunction "2_2") (pintype "passive"))
      (node (ref "R148") (pin "2") (pinfunction "2_2") (pintype "passive"))
      (node (ref "R155") (pin "2") (pinfunction "2_2") (pintype "passive"))
      (node (ref "R156") (pin "2") (pinfunction "2_2") (pintype "passive"))
      (node (ref "U10") (pin "24") (pinfunction "+VBD_24") (pintype "passive"))
      (node (ref "U10") (pin "34") (pinfunction "+VBD_34") (pintype "passive"))
      (node (ref "U10") (pin "37") (pinfunction "+VBD_37") (pintype "passive"))
      (node (ref "U17") (pin "24") (pinfunction "+VBD_24") (pintype "passive"))
      (node (ref "U17") (pin "34") (pinfunction "+VBD_34") (pintype "passive"))
      (node (ref "U17") (pin "37") (pinfunction "+VBD_37") (pintype "passive"))
      (node (ref "U2") (pin "100") (pinfunction "VDD_3_100") (pintype "passive"))
      (node (ref "U2") (pin "11") (pinfunction "Vdd_5_11") (pintype "passive"))
      (node (ref "U2") (pin "22") (pinfunction "VDDA_22") (pintype "passive"))
      (node (ref "U2") (pin "28") (pinfunction "VDD_4_28") (pintype "passive"))
      (node (ref "U2") (pin "50") (pinfunction "VDD_1_50") (pintype "passive"))
      (node (ref "U2") (pin "6") (pinfunction "Vbat_6") (pintype "passive"))
      (node (ref "U2") (pin "75") (pinfunction "VDD_2_75") (pintype "passive"))
    )
    (net (code "73") (name "3.3VCC_REF_1") (class "Default")
      (node (ref "U2") (pin "21") (pinfunction "Vref+_21") (pintype "passive"))
    )
    (net (code "74") (name "AGND1") (class "Default")
      (node (ref "C52") (pin "2") (pinfunction "2_2") (pintype "passive"))
      (node (ref "C53") (pin "2") (pinfunction "2_2") (pintype "passive"))
      (node (ref "C73") (pin "1") (pinfunction "1_1") (pintype "passive"))
      (node (ref "C74") (pin "1") (pinfunction "1_1") (pintype "passive"))
      (node (ref "C75") (pin "1") (pinfunction "1_1") (pintype "passive"))
      (node (ref "C76") (pin "1") (pinfunction "1_1") (pintype "passive"))
      (node (ref "C77") (pin "1") (pinfunction "1_1") (pintype "passive"))
      (node (ref "C78") (pin "1") (pinfunction "1_1") (pintype "passive"))
      (node (ref "C79") (pin "1") (pinfunction "1_1") (pintype "passive"))
      (node (ref "FB15") (pin "2") (pinfunction "2_2") (pintype "passive"))
      (node (ref "U17") (pin "11") (pinfunction "AGND_11") (pintype "passive"))
      (node (ref "U17") (pin "12") (pinfunction "AGND_12") (pintype "passive"))
      (node (ref "U17") (pin "14") (pinfunction "AGND_14") (pintype "passive"))
      (node (ref "U17") (pin "15") (pinfunction "AGND_15") (pintype "passive"))
      (node (ref "U17") (pin "44") (pinfunction "AGND_44") (pintype "passive"))
      (node (ref "U17") (pin "45") (pinfunction "AGND_45") (pintype "passive"))
      (node (ref "U17") (pin "47") (pinfunction "REFM_47") (pintype "passive"))
      (node (ref "U17") (pin "48") (pinfunction "REFM_48") (pintype "passive"))
      (node (ref "U17") (pin "5") (pinfunction "AGND_5") (pintype "passive"))
      (node (ref "U17") (pin "7") (pinfunction "-IN_7") (pintype "passive"))
      (node (ref "U17") (pin "8") (pinfunction "AGND_8") (pintype "passive"))
    )
    (net (code "75") (name "AGND2") (class "Default")
      (node (ref "C100") (pin "1") (pinfunction "1_1") (pintype "passive"))
      (node (ref "C63") (pin "2") (pinfunction "2_2") (pintype "passive"))
      (node (ref "C64") (pin "2") (pinfunction "2_2") (pintype "passive"))
      (node (ref "C91") (pin "1") (pinfunction "1_1") (pintype "passive"))
      (node (ref "C92") (pin "1") (pinfunction "1_1") (pintype "passive"))
      (node (ref "C96") (pin "1") (pinfunction "1_1") (pintype "passive"))
      (node (ref "C97") (pin "1") (pinfunction "1_1") (pintype "passive"))
      (node (ref "C98") (pin "1") (pinfunction "1_1") (pintype "passive"))
      (node (ref "C99") (pin "1") (pinfunction "1_1") (pintype "passive"))
      (node (ref "FB28") (pin "2") (pinfunction "2_2") (pintype "passive"))
      (node (ref "U10") (pin "11") (pinfunction "AGND_11") (pintype "passive"))
      (node (ref "U10") (pin "12") (pinfunction "AGND_12") (pintype "passive"))
      (node (ref "U10") (pin "14") (pinfunction "AGND_14") (pintype "passive"))
      (node (ref "U10") (pin "15") (pinfunction "AGND_15") (pintype "passive"))
      (node (ref "U10") (pin "44") (pinfunction "AGND_44") (pintype "passive"))
      (node (ref "U10") (pin "45") (pinfunction "AGND_45") (pintype "passive"))
      (node (ref "U10") (pin "47") (pinfunction "REFM_47") (pintype "passive"))
      (node (ref "U10") (pin "48") (pinfunction "REFM_48") (pintype "passive"))
      (node (ref "U10") (pin "5") (pinfunction "AGND_5") (pintype "passive"))
      (node (ref "U10") (pin "7") (pinfunction "-IN_7") (pintype "passive"))
      (node (ref "U10") (pin "8") (pinfunction "AGND_8") (pintype "passive"))
    )
    (net (code "76") (name "GND") (class "Default")
      (node (ref "C25") (pin "1") (pinfunction "1_1") (pintype "passive"))
      (node (ref "C26") (pin "1") (pinfunction "1_1") (pintype "passive"))
      (node (ref "C29") (pin "1") (pinfunction "1_1") (pintype "passive"))
      (node (ref "C50") (pin "1") (pinfunction "1_1") (pintype "passive"))
      (node (ref "C51") (pin "1") (pinfunction "1_1") (pintype "passive"))
      (node (ref "C54") (pin "1") (pinfunction "1_1") (pintype "passive"))
      (node (ref "C58") (pin "1") (pinfunction "1_1") (pintype "passive"))
      (node (ref "C59") (pin "1") (pinfunction "1_1") (pintype "passive"))
      (node (ref "C60") (pin "1") (pinfunction "1_1") (pintype "passive"))
      (node (ref "C61") (pin "2") (pinfunction "2_2") (pintype "passive"))
      (node (ref "C62") (pin "2") (pinfunction "2_2") (pintype "passive"))
      (node (ref "C65") (pin "1") (pinfunction "1_1") (pintype "passive"))
      (node (ref "C66") (pin "1") (pinfunction "1_1") (pintype "passive"))
      (node (ref "C67") (pin "1") (pinfunction "1_1") (pintype "passive"))
      (node (ref "C68") (pin "1") (pinfunction "1_1") (pintype "passive"))
      (node (ref "C69") (pin "1") (pinfunction "1_1") (pintype "passive"))
      (node (ref "C70") (pin "1") (pinfunction "1_1") (pintype "passive"))
      (node (ref "C71") (pin "1") (pinfunction "1_1") (pintype "passive"))
      (node (ref "C72") (pin "1") (pinfunction "1_1") (pintype "passive"))
      (node (ref "FB15") (pin "1") (pinfunction "1_1") (pintype "passive"))
      (node (ref "FB28") (pin "1") (pinfunction "1_1") (pintype "passive"))
      (node (ref "J10") (pin "13") (pinfunction "13_13") (pintype "passive"))
      (node (ref "J10") (pin "14") (pinfunction "14_14") (pintype "passive"))
      (node (ref "J10") (pin "6") (pinfunction "RX-_6") (pintype "passive"))
      (node (ref "J11") (pin "6") (pinfunction "6_6") (pintype "passive"))
      (node (ref "R145") (pin "1") (pinfunction "1_1") (pintype "passive"))
      (node (ref "R157") (pin "1") (pinfunction "1_1") (pintype "passive"))
      (node (ref "R164") (pin "1") (pinfunction "1_1") (pintype "passive"))
      (node (ref "U10") (pin "25") (pinfunction "BDGND_25") (pintype "passive"))
      (node (ref "U10") (pin "35") (pinfunction "BDGND_35") (pintype "passive"))
      (node (ref "U17") (pin "25") (pinfunction "BDGND_25") (pintype "passive"))
      (node (ref "U17") (pin "35") (pinfunction "BDGND_35") (pintype "passive"))
      (node (ref "U2") (pin "10") (pinfunction "Vss_5_10") (pintype "passive"))
      (node (ref "U2") (pin "19") (pinfunction "VssA_19") (pintype "passive"))
      (node (ref "U2") (pin "20") (pinfunction "Vref-_20") (pintype "passive"))
      (node (ref "U2") (pin "27") (pinfunction "VSS_4_27") (pintype "passive"))
      (node (ref "U2") (pin "49") (pinfunction "VSS_1_49") (pintype "passive"))
      (node (ref "U2") (pin "74") (pinfunction "VSS-2_74") (pintype "passive"))
      (node (ref "U2") (pin "99") (pinfunction "VSS_3_99") (pintype "passive"))
    )
    (net (code "77") (name "Net-(TP4-TP)") (class "Default")
      (node (ref "TP4") (pin "1") (pinfunction "TP_1") (pintype "passive"))
      (node (ref "U2") (pin "69") (pinfunction "PA10/USART1_RX/TIM1_CH3_69") (pintype "passive"))
    )
    (net (code "78") (name "Net-(TP5-TP)") (class "Default")
      (node (ref "TP5") (pin "1") (pinfunction "TP_1") (pintype "passive"))
      (node (ref "U2") (pin "68") (pinfunction "PA9/USART1_TX/TIM1_CH2_68") (pintype "passive"))
    )
    (net (code "79") (name "Net-(TP6-TP)") (class "Default")
      (node (ref "TP6") (pin "1") (pinfunction "TP_1") (pintype "passive"))
      (node (ref "U2") (pin "67") (pinfunction "PA8/USART1_CK/TIM1_CH1/MCO_67") (pintype "passive"))
    )
    (net (code "80") (name "Net-(TP12-TP)") (class "Default")
      (node (ref "TP12") (pin "1") (pinfunction "TP_1") (pintype "passive"))
      (node (ref "U2") (pin "93") (pinfunction "PB7/IC21_SDA/TIM4_CH2_93") (pintype "passive"))
    )
    (net (code "81") (name "Net-(TP13-TP)") (class "Default")
      (node (ref "TP13") (pin "1") (pinfunction "TP_1") (pintype "passive"))
      (node (ref "U2") (pin "92") (pinfunction "PB6/I2C1_SCL/TIM4_CH1_92") (pintype "passive"))
    )
    (net (code "82") (name "Net-(U2-BOOT0)") (class "Default")
      (node (ref "R145") (pin "2") (pinfunction "2_2") (pintype "passive"))
      (node (ref "U2") (pin "94") (pinfunction "BOOT0_94") (pintype "passive"))
    )
    (net (code "83") (name "Net-(U2-OSC_IN)") (class "Default")
      (node (ref "C61") (pin "1") (pinfunction "1_1") (pintype "passive"))
      (node (ref "U2") (pin "12") (pinfunction "OSC_IN_12") (pintype "passive"))
      (node (ref "X1") (pin "2") (pinfunction "OSC2_2") (pintype "passive"))
    )
    (net (code "84") (name "Net-(U2-OSC_OUT)") (class "Default")
      (node (ref "C62") (pin "1") (pinfunction "1_1") (pintype "passive"))
      (node (ref "U2") (pin "13") (pinfunction "OSC_OUT_13") (pintype "passive"))
      (node (ref "X1") (pin "1") (pinfunction "OSC1_1") (pintype "passive"))
    )
    (net (code "85") (name "Net-(U2-PB2{slash}BOOT1)") (class "Default")
      (node (ref "R164") (pin "2") (pinfunction "2_2") (pintype "passive"))
      (node (ref "U2") (pin "37") (pinfunction "PB2/BOOT1_37") (pintype "passive"))
    )
    (net (code "86") (name "Net-(U10-BUSY)") (class "Default")
      (node (ref "R237") (pin "1") (pinfunction "1_1") (pintype "passive"))
      (node (ref "U10") (pin "36") (pinfunction "BUSY_36") (pintype "passive"))
    )
    (net (code "87") (name "Net-(U10-BYTE)") (class "Default")
      (node (ref "R235") (pin "1") (pinfunction "1_1") (pintype "passive"))
      (node (ref "U10") (pin "39") (pinfunction "BYTE_39") (pintype "passive"))
    )
    (net (code "88") (name "Net-(U10-DB0)") (class "Default")
      (node (ref "R238") (pin "1") (pinfunction "1_1") (pintype "passive"))
      (node (ref "U10") (pin "33") (pinfunction "DB0_33") (pintype "passive"))
    )
    (net (code "89") (name "Net-(U10-DB1)") (class "Default")
      (node (ref "R239") (pin "1") (pinfunction "1_1") (pintype "passive"))
      (node (ref "U10") (pin "32") (pinfunction "DB1_32") (pintype "passive"))
    )
    (net (code "90") (name "Net-(U10-DB2)") (class "Default")
      (node (ref "R240") (pin "1") (pinfunction "1_1") (pintype "passive"))
      (node (ref "U10") (pin "31") (pinfunction "DB2_31") (pintype "passive"))
    )
    (net (code "91") (name "Net-(U10-DB3)") (class "Default")
      (node (ref "R241") (pin "1") (pinfunction "1_1") (pintype "passive"))
      (node (ref "U10") (pin "30") (pinfunction "DB3_30") (pintype "passive"))
    )
    (net (code "92") (name "Net-(U10-DB4)") (class "Default")
      (node (ref "R242") (pin "1") (pinfunction "1_1") (pintype "passive"))
      (node (ref "U10") (pin "29") (pinfunction "DB4_29") (pintype "passive"))
    )
    (net (code "93") (name "Net-(U10-DB5)") (class "Default")
      (node (ref "R243") (pin "1") (pinfunction "1_1") (pintype "passive"))
      (node (ref "U10") (pin "28") (pinfunction "DB5_28") (pintype "passive"))
    )
    (net (code "94") (name "Net-(U10-DB6)") (class "Default")
      (node (ref "R244") (pin "1") (pinfunction "1_1") (pintype "passive"))
      (node (ref "U10") (pin "27") (pinfunction "DB6_27") (pintype "passive"))
    )
    (net (code "95") (name "Net-(U10-DB7)") (class "Default")
      (node (ref "R245") (pin "1") (pinfunction "1_1") (pintype "passive"))
      (node (ref "U10") (pin "26") (pinfunction "DB7_26") (pintype "passive"))
    )
    (net (code "96") (name "Net-(U10-DB8)") (class "Default")
      (node (ref "R253") (pin "2") (pinfunction "2_2") (pintype "passive"))
      (node (ref "U10") (pin "23") (pinfunction "DB8_23") (pintype "passive"))
    )
    (net (code "97") (name "Net-(U10-DB9)") (class "Default")
      (node (ref "R252") (pin "2") (pinfunction "2_2") (pintype "passive"))
      (node (ref "U10") (pin "22") (pinfunction "DB9_22") (pintype "passive"))
    )
    (net (code "98") (name "Net-(U10-DB10)") (class "Default")
      (node (ref "R251") (pin "2") (pinfunction "2_2") (pintype "passive"))
      (node (ref "U10") (pin "21") (pinfunction "DB10_21") (pintype "passive"))
    )
    (net (code "99") (name "Net-(U10-DB11)") (class "Default")
      (node (ref "R250") (pin "2") (pinfunction "2_2") (pintype "passive"))
      (node (ref "U10") (pin "20") (pinfunction "DB11_20") (pintype "passive"))
    )
    (net (code "100") (name "Net-(U10-DB12)") (class "Default")
      (node (ref "R249") (pin "2") (pinfunction "2_2") (pintype "passive"))
      (node (ref "U10") (pin "19") (pinfunction "DB12_19") (pintype "passive"))
    )
    (net (code "101") (name "Net-(U10-DB13)") (class "Default")
      (node (ref "R248") (pin "2") (pinfunction "2_2") (pintype "passive"))
      (node (ref "U10") (pin "18") (pinfunction "DB13_18") (pintype "passive"))
    )
    (net (code "102") (name "Net-(U10-DB14)") (class "Default")
      (node (ref "R247") (pin "2") (pinfunction "2_2") (pintype "passive"))
      (node (ref "U10") (pin "17") (pinfunction "DB14_17") (pintype "passive"))
    )
    (net (code "103") (name "Net-(U10-DB15)") (class "Default")
      (node (ref "R246") (pin "2") (pinfunction "2_2") (pintype "passive"))
      (node (ref "U10") (pin "16") (pinfunction "DB15_16") (pintype "passive"))
    )
    (net (code "104") (name "Net-(U10-REFIN)") (class "Default")
      (node (ref "C63") (pin "1") (pinfunction "1_1") (pintype "passive"))
      (node (ref "C64") (pin "1") (pinfunction "1_1") (pintype "passive"))
      (node (ref "FB27") (pin "1") (pinfunction "1_1") (pintype "passive"))
      (node (ref "U10") (pin "1") (pinfunction "REFIN_1") (pintype "passive"))
    )
    (net (code "105") (name "Net-(U10-REFOUT)") (class "Default")
      (node (ref "FB27") (pin "2") (pinfunction "2_2") (pintype "passive"))
      (node (ref "U10") (pin "2") (pinfunction "REFOUT_2") (pintype "passive"))
    )
    (net (code "106") (name "Net-(U10-~{CONVST})") (class "Default")
      (node (ref "R234") (pin "1") (pinfunction "1_1") (pintype "passive"))
      (node (ref "U10") (pin "40") (pinfunction "~{CONVST}_40") (pintype "passive"))
    )
    (net (code "107") (name "Net-(U10-~{CS})") (class "Default")
      (node (ref "R232") (pin "1") (pinfunction "1_1") (pintype "passive"))
      (node (ref "U10") (pin "42") (pinfunction "~{CS}_42") (pintype "passive"))
    )
    (net (code "108") (name "Net-(U10-~{RD})") (class "Default")
      (node (ref "R233") (pin "1") (pinfunction "1_1") (pintype "passive"))
      (node (ref "U10") (pin "41") (pinfunction "~{RD}_41") (pintype "passive"))
    )
    (net (code "109") (name "Net-(U10-~{RESET})") (class "Default")
      (node (ref "R236") (pin "1") (pinfunction "1_1") (pintype "passive"))
      (node (ref "U10") (pin "38") (pinfunction "~{RESET}_38") (pintype "passive"))
    )
    (net (code "110") (name "Net-(U17-BUSY)") (class "Default")
      (node (ref "R117") (pin "1") (pinfunction "1_1") (pintype "passive"))
      (node (ref "U17") (pin "36") (pinfunction "BUSY_36") (pintype "passive"))
    )
    (net (code "111") (name "Net-(U17-BYTE)") (class "Default")
      (node (ref "R112") (pin "1") (pinfunction "1_1") (pintype "passive"))
      (node (ref "U17") (pin "39") (pinfunction "BYTE_39") (pintype "passive"))
    )
    (net (code "112") (name "Net-(U17-DB0)") (class "Default")
      (node (ref "R118") (pin "1") (pinfunction "1_1") (pintype "passive"))
      (node (ref "U17") (pin "33") (pinfunction "DB0_33") (pintype "passive"))
    )
    (net (code "113") (name "Net-(U17-DB1)") (class "Default")
      (node (ref "R122") (pin "1") (pinfunction "1_1") (pintype "passive"))
      (node (ref "U17") (pin "32") (pinfunction "DB1_32") (pintype "passive"))
    )
    (net (code "114") (name "Net-(U17-DB2)") (class "Default")
      (node (ref "R124") (pin "1") (pinfunction "1_1") (pintype "passive"))
      (node (ref "U17") (pin "31") (pinfunction "DB2_31") (pintype "passive"))
    )
    (net (code "115") (name "Net-(U17-DB3)") (class "Default")
      (node (ref "R125") (pin "1") (pinfunction "1_1") (pintype "passive"))
      (node (ref "U17") (pin "30") (pinfunction "DB3_30") (pintype "passive"))
    )
    (net (code "116") (name "Net-(U17-DB4)") (class "Default")
      (node (ref "R126") (pin "1") (pinfunction "1_1") (pintype "passive"))
      (node (ref "U17") (pin "29") (pinfunction "DB4_29") (pintype "passive"))
    )
    (net (code "117") (name "Net-(U17-DB5)") (class "Default")
      (node (ref "R130") (pin "1") (pinfunction "1_1") (pintype "passive"))
      (node (ref "U17") (pin "28") (pinfunction "DB5_28") (pintype "passive"))
    )
    (net (code "118") (name "Net-(U17-DB6)") (class "Default")
      (node (ref "R131") (pin "1") (pinfunction "1_1") (pintype "passive"))
      (node (ref "U17") (pin "27") (pinfunction "DB6_27") (pintype "passive"))
    )
    (net (code "119") (name "Net-(U17-DB7)") (class "Default")
      (node (ref "R132") (pin "1") (pinfunction "1_1") (pintype "passive"))
      (node (ref "U17") (pin "26") (pinfunction "DB7_26") (pintype "passive"))
    )
    (net (code "120") (name "Net-(U17-DB8)") (class "Default")
      (node (ref "R140") (pin "2") (pinfunction "2_2") (pintype "passive"))
      (node (ref "U17") (pin "23") (pinfunction "DB8_23") (pintype "passive"))
    )
    (net (code "121") (name "Net-(U17-DB9)") (class "Default")
      (node (ref "R139") (pin "2") (pinfunction "2_2") (pintype "passive"))
      (node (ref "U17") (pin "22") (pinfunction "DB9_22") (pintype "passive"))
    )
    (net (code "122") (name "Net-(U17-DB10)") (class "Default")
      (node (ref "R138") (pin "2") (pinfunction "2_2") (pintype "passive"))
      (node (ref "U17") (pin "21") (pinfunction "DB10_21") (pintype "passive"))
    )
    (net (code "123") (name "Net-(U17-DB11)") (class "Default")
      (node (ref "R137") (pin "2") (pinfunction "2_2") (pintype "passive"))
      (node (ref "U17") (pin "20") (pinfunction "DB11_20") (pintype "passive"))
    )
    (net (code "124") (name "Net-(U17-DB12)") (class "Default")
      (node (ref "R136") (pin "2") (pinfunction "2_2") (pintype "passive"))
      (node (ref "U17") (pin "19") (pinfunction "DB12_19") (pintype "passive"))
    )
    (net (code "125") (name "Net-(U17-DB13)") (class "Default")
      (node (ref "R135") (pin "2") (pinfunction "2_2") (pintype "passive"))
      (node (ref "U17") (pin "18") (pinfunction "DB13_18") (pintype "passive"))
    )
    (net (code "126") (name "Net-(U17-DB14)") (class "Default")
      (node (ref "R134") (pin "2") (pinfunction "2_2") (pintype "passive"))
      (node (ref "U17") (pin "17") (pinfunction "DB14_17") (pintype "passive"))
    )
    (net (code "127") (name "Net-(U17-DB15)") (class "Default")
      (node (ref "R133") (pin "2") (pinfunction "2_2") (pintype "passive"))
      (node (ref "U17") (pin "16") (pinfunction "DB15_16") (pintype "passive"))
    )
    (net (code "128") (name "Net-(U17-REFIN)") (class "Default")
      (node (ref "C52") (pin "1") (pinfunction "1_1") (pintype "passive"))
      (node (ref "C53") (pin "1") (pinfunction "1_1") (pintype "passive"))
      (node (ref "FB14") (pin "1") (pinfunction "1_1") (pintype "passive"))
      (node (ref "U17") (pin "1") (pinfunction "REFIN_1") (pintype "passive"))
    )
    (net (code "129") (name "Net-(U17-REFOUT)") (class "Default")
      (node (ref "FB14") (pin "2") (pinfunction "2_2") (pintype "passive"))
      (node (ref "U17") (pin "2") (pinfunction "REFOUT_2") (pintype "passive"))
    )
    (net (code "130") (name "Net-(U17-~{CONVST})") (class "Default")
      (node (ref "R99") (pin "1") (pinfunction "1_1") (pintype "passive"))
      (node (ref "U17") (pin "40") (pinfunction "~{CONVST}_40") (pintype "passive"))
    )
    (net (code "131") (name "Net-(U17-~{CS})") (class "Default")
      (node (ref "R48") (pin "1") (pinfunction "1_1") (pintype "passive"))
      (node (ref "U17") (pin "42") (pinfunction "~{CS}_42") (pintype "passive"))
    )
    (net (code "132") (name "Net-(U17-~{RD})") (class "Default")
      (node (ref "R60") (pin "1") (pinfunction "1_1") (pintype "passive"))
      (node (ref "U17") (pin "41") (pinfunction "~{RD}_41") (pintype "passive"))
    )
    (net (code "133") (name "Net-(U17-~{RESET})") (class "Default")
      (node (ref "R114") (pin "1") (pinfunction "1_1") (pintype "passive"))
      (node (ref "U17") (pin "38") (pinfunction "~{RESET}_38") (pintype "passive"))
    )
    (net (code "134") (name "unconnected-(J10-A1-Pad10)") (class "Default")
      (node (ref "J10") (pin "10") (pinfunction "A1_10") (pintype "passive"))
    )
    (net (code "135") (name "unconnected-(J10-A2-Pad12)") (class "Default")
      (node (ref "J10") (pin "12") (pinfunction "A2_12") (pintype "passive"))
    )
    (net (code "136") (name "unconnected-(J10-K1-Pad9)") (class "Default")
      (node (ref "J10") (pin "9") (pinfunction "K1_9") (pintype "passive"))
    )
    (net (code "137") (name "unconnected-(J10-K2-Pad11)") (class "Default")
      (node (ref "J10") (pin "11") (pinfunction "K2_11") (pintype "passive"))
    )
    (net (code "138") (name "unconnected-(J10-Pad15)") (class "Default")
      (node (ref "J10") (pin "15") (pinfunction "15_15") (pintype "passive+no_connect"))
    )
    (net (code "139") (name "unconnected-(J10-Pad16)") (class "Default")
      (node (ref "J10") (pin "16") (pinfunction "16_16") (pintype "passive+no_connect"))
    )
    (net (code "140") (name "unconnected-(U2-NC-Pad73)") (class "Default")
      (node (ref "U2") (pin "73") (pinfunction "NC_73") (pintype "passive"))
    )
    (net (code "141") (name "unconnected-(U2-PA0{slash}WKUP{slash}USART2_CTS{slash}ADC_IN0{slash}TIM2_CH1_ETR-Pad23)") (class "Default")
      (node (ref "U2") (pin "23") (pinfunction "PA0/WKUP/USART2_CTS/ADC_IN0/TIM2_CH1_ETR_23") (pintype "passive"))
    )
    (net (code "142") (name "unconnected-(U2-PA1{slash}USART2_RTS{slash}ADC_IN1{slash}TIM2_CH2-Pad24)") (class "Default")
      (node (ref "U2") (pin "24") (pinfunction "PA1/USART2_RTS/ADC_IN1/TIM2_CH2_24") (pintype "passive"))
    )
    (net (code "143") (name "unconnected-(U2-PA11{slash}USART1_CTS{slash}CANRX{slash}USBDM{slash}TIM1_CH4-Pad70)") (class "Default")
      (node (ref "U2") (pin "70") (pinfunction "PA11/USART1_CTS/CANRX/USBDM/TIM1_CH4_70") (pintype "passive"))
    )
    (net (code "144") (name "unconnected-(U2-PA12{slash}USART1_RTS{slash}CANTX{slash}USBDP{slash}TIM1_ETR-Pad71)") (class "Default")
      (node (ref "U2") (pin "71") (pinfunction "PA12/USART1_RTS/CANTX/USBDP/TIM1_ETR_71") (pintype "passive"))
    )
    (net (code "145") (name "unconnected-(U2-PB0{slash}ADC_IN8{slash}TIM3_CH3-Pad35)") (class "Default")
      (node (ref "U2") (pin "35") (pinfunction "PB0/ADC_IN8/TIM3_CH3_35") (pintype "passive"))
    )
    (net (code "146") (name "unconnected-(U2-PB1{slash}ADC_IN9{slash}TIM3_CH4-Pad36)") (class "Default")
      (node (ref "U2") (pin "36") (pinfunction "PB1/ADC_IN9/TIM3_CH4_36") (pintype "passive"))
    )
    (net (code "147") (name "unconnected-(U2-PB5{slash}I2C1_SMBAI-Pad91)") (class "Default")
      (node (ref "U2") (pin "91") (pinfunction "PB5/I2C1_SMBAI_91") (pintype "passive"))
    )
    (net (code "148") (name "unconnected-(U2-PB8{slash}TIM4_CH3-Pad95)") (class "Default")
      (node (ref "U2") (pin "95") (pinfunction "PB8/TIM4_CH3_95") (pintype "passive"))
    )
    (net (code "149") (name "unconnected-(U2-PB9{slash}TIM4_CH4-Pad96)") (class "Default")
      (node (ref "U2") (pin "96") (pinfunction "PB9/TIM4_CH4_96") (pintype "passive"))
    )
    (net (code "150") (name "unconnected-(U10-NC-Pad3)") (class "Default")
      (node (ref "U10") (pin "3") (pinfunction "NC_3") (pintype "passive+no_connect"))
    )
    (net (code "151") (name "unconnected-(U17-NC-Pad3)") (class "Default")
      (node (ref "U17") (pin "3") (pinfunction "NC_3") (pintype "passive+no_connect"))
    )
  )
)
